# slave-board.net
KiCad netlist of a schematic drawn in EAGLE
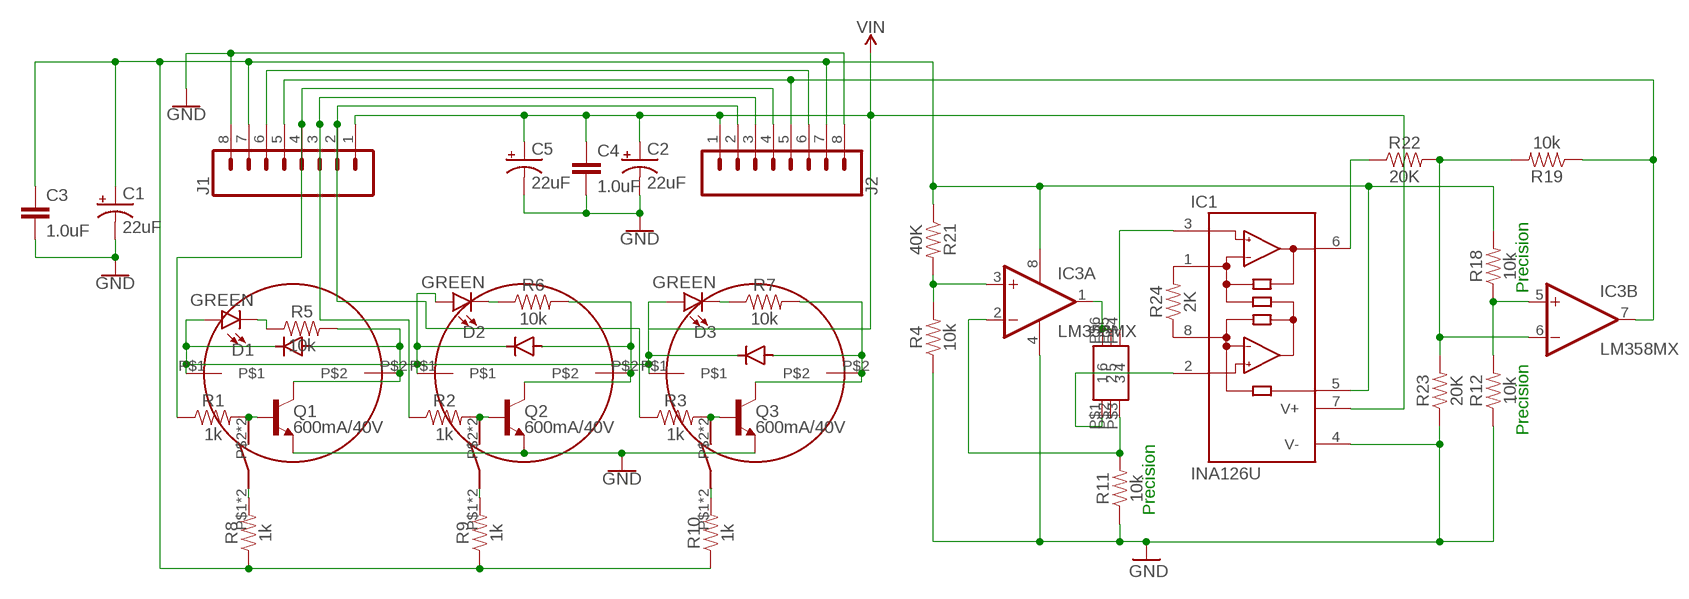
[diagram p0: schematic, sheet 1]

(export (version "E")
  (design (tool "Eeschema 10.0.6"))
  (components
    (comp (ref "C1")
      (value "22uF")
      (footprint "eagle-import:PANASONIC_C")
      (libsource (lib "eagle-import") (part "22UF-POLAR-PANASONIC_C-35V-20%"))
    )
    (comp (ref "C2")
      (value "22uF")
      (footprint "eagle-import:PANASONIC_C")
      (libsource (lib "eagle-import") (part "22UF-POLAR-PANASONIC_C-35V-20%"))
    )
    (comp (ref "C3")
      (value "1.0uF")
      (footprint "eagle-import:0603")
      (libsource (lib "eagle-import") (part "1.0UF-0603-16V-10%"))
    )
    (comp (ref "C4")
      (value "1.0uF")
      (footprint "eagle-import:0603")
      (libsource (lib "eagle-import") (part "1.0UF-0603-16V-10%"))
    )
    (comp (ref "C5")
      (value "22uF")
      (footprint "eagle-import:PANASONIC_C")
      (libsource (lib "eagle-import") (part "22UF-POLAR-PANASONIC_C-35V-20%"))
    )
    (comp (ref "D1")
      (value "GREEN")
      (footprint "eagle-import:LED-0603")
      (libsource (lib "eagle-import") (part "LED-GREEN0603"))
    )
    (comp (ref "D2")
      (value "GREEN")
      (footprint "eagle-import:LED-0603")
      (libsource (lib "eagle-import") (part "LED-GREEN0603"))
    )
    (comp (ref "D3")
      (value "GREEN")
      (footprint "eagle-import:LED-0603")
      (libsource (lib "eagle-import") (part "LED-GREEN0603"))
    )
    (comp (ref "IC1")
      (value "INA126U")
      (footprint "eagle-import:SO08")
      (fields (field (name "MF") "Texas Instruments") (field (name "MP") "INA126"))
      (libsource (lib "eagle-import") (part "INA126U"))
    )
    (comp (ref "IC3")
      (value "LM358MX")
      (footprint "eagle-import:SO08")
      (libsource (lib "eagle-import") (part "LM358MX"))
    )
    (comp (ref "J1")
      (value "CONN_08\"")
      (footprint "eagle-import:1X08")
      (libsource (lib "eagle-import") (part "CONN_08{dblquote}"))
    )
    (comp (ref "J2")
      (value "CONN_08\"")
      (footprint "eagle-import:1X08")
      (libsource (lib "eagle-import") (part "CONN_08{dblquote}"))
    )
    (comp (ref "Q1")
      (value "600mA/40V")
      (footprint "eagle-import:SOT23-3")
      (libsource (lib "eagle-import") (part "TRANS_NPN-MMBT2222AL"))
    )
    (comp (ref "Q2")
      (value "600mA/40V")
      (footprint "eagle-import:SOT23-3")
      (libsource (lib "eagle-import") (part "TRANS_NPN-MMBT2222AL"))
    )
    (comp (ref "Q3")
      (value "600mA/40V")
      (footprint "eagle-import:SOT23-3")
      (libsource (lib "eagle-import") (part "TRANS_NPN-MMBT2222AL"))
    )
    (comp (ref "R1")
      (value "1k")
      (footprint "eagle-import:0603")
      (libsource (lib "eagle-import") (part "1KOHM-0603-1/10W-1%"))
    )
    (comp (ref "R2")
      (value "1k")
      (footprint "eagle-import:0603")
      (libsource (lib "eagle-import") (part "1KOHM-0603-1/10W-1%"))
    )
    (comp (ref "R3")
      (value "1k")
      (footprint "eagle-import:0603")
      (libsource (lib "eagle-import") (part "1KOHM-0603-1/10W-1%"))
    )
    (comp (ref "R4")
      (value "10k")
      (footprint "eagle-import:0603")
      (libsource (lib "eagle-import") (part "10KOHM-0603-1/10W-1%"))
    )
    (comp (ref "R5")
      (value "10k")
      (footprint "eagle-import:0603")
      (libsource (lib "eagle-import") (part "10KOHM-0603-1/10W-1%"))
    )
    (comp (ref "R6")
      (value "10k")
      (footprint "eagle-import:0603")
      (libsource (lib "eagle-import") (part "10KOHM-0603-1/10W-1%"))
    )
    (comp (ref "R7")
      (value "10k")
      (footprint "eagle-import:0603")
      (libsource (lib "eagle-import") (part "10KOHM-0603-1/10W-1%"))
    )
    (comp (ref "R8")
      (value "1k")
      (footprint "eagle-import:0603")
      (libsource (lib "eagle-import") (part "1KOHM-0603-1/10W-1%"))
    )
    (comp (ref "R9")
      (value "1k")
      (footprint "eagle-import:0603")
      (libsource (lib "eagle-import") (part "1KOHM-0603-1/10W-1%"))
    )
    (comp (ref "R10")
      (value "1k")
      (footprint "eagle-import:0603")
      (libsource (lib "eagle-import") (part "1KOHM-0603-1/10W-1%"))
    )
    (comp (ref "R11")
      (value "10k")
      (footprint "eagle-import:0603")
      (libsource (lib "eagle-import") (part "10KOHM-0603-1/10W-1%"))
    )
    (comp (ref "R12")
      (value "10k")
      (footprint "eagle-import:0603")
      (libsource (lib "eagle-import") (part "10KOHM-0603-1/10W-1%"))
    )
    (comp (ref "R18")
      (value "10k")
      (footprint "eagle-import:0603")
      (libsource (lib "eagle-import") (part "10KOHM-0603-1/10W-1%"))
    )
    (comp (ref "R19")
      (value "10k")
      (footprint "eagle-import:0603")
      (libsource (lib "eagle-import") (part "10KOHM-0603-1/10W-1%"))
    )
    (comp (ref "R21")
      (value "40K")
      (footprint "eagle-import:0603")
      (libsource (lib "eagle-import") (part "10KOHM-0603-1/10W-1%"))
    )
    (comp (ref "R22")
      (value "20K")
      (footprint "eagle-import:0603")
      (libsource (lib "eagle-import") (part "10KOHM-0603-1/10W-1%"))
    )
    (comp (ref "R23")
      (value "20K")
      (footprint "eagle-import:0603")
      (libsource (lib "eagle-import") (part "10KOHM-0603-1/10W-1%"))
    )
    (comp (ref "R24")
      (value "2K")
      (footprint "eagle-import:0603")
      (libsource (lib "eagle-import") (part "10KOHM-0603-1/10W-1%"))
    )
    (comp (ref "U$1")
      (value "2SMPP-03")
      (footprint "eagle-import:2SMPP-03")
      (libsource (lib "eagle-import") (part "2SMPP-03"))
    )
    (comp (ref "U$2")
      (value "CJV23-SOLENOID-VALVE")
      (footprint "eagle-import:CJV23")
      (libsource (lib "eagle-import") (part "CJV23-SOLENOID-VALVE"))
    )
    (comp (ref "U$3")
      (value "CJV23-SOLENOID-VALVE")
      (footprint "eagle-import:CJV23")
      (libsource (lib "eagle-import") (part "CJV23-SOLENOID-VALVE"))
    )
    (comp (ref "U$4")
      (value "CJV23-SOLENOID-VALVE")
      (footprint "eagle-import:CJV23")
      (libsource (lib "eagle-import") (part "CJV23-SOLENOID-VALVE"))
    )
    (comp (ref "U$5")
      (value "IN4148")
      (footprint "eagle-import:IN4148")
      (libsource (lib "eagle-import") (part "IN4148"))
    )
    (comp (ref "U$6")
      (value "IN4148")
      (footprint "eagle-import:IN4148")
      (libsource (lib "eagle-import") (part "IN4148"))
    )
    (comp (ref "U$7")
      (value "IN4148")
      (footprint "eagle-import:IN4148")
      (libsource (lib "eagle-import") (part "IN4148"))
    )
    (comp (ref "U$8")
      (value "BUTTON")
      (footprint "eagle-import:BUTTON")
      (libsource (lib "eagle-import") (part "BUTTON"))
    )
    (comp (ref "U$9")
      (value "BUTTON")
      (footprint "eagle-import:BUTTON")
      (libsource (lib "eagle-import") (part "BUTTON"))
    )
    (comp (ref "U$10")
      (value "BUTTON")
      (footprint "eagle-import:BUTTON")
      (libsource (lib "eagle-import") (part "BUTTON"))
    )
  )
  (nets
    (net (code "1") (name "GND") (class "Default")
      (node (ref "C1") (pin "-") (pinfunction "-_-") (pintype "passive"))
      (node (ref "C2") (pin "-") (pinfunction "-_-") (pintype "passive"))
      (node (ref "C3") (pin "2") (pinfunction "2_2") (pintype "passive"))
      (node (ref "C4") (pin "2") (pinfunction "2_2") (pintype "passive"))
      (node (ref "C5") (pin "-") (pinfunction "-_-") (pintype "passive"))
      (node (ref "IC1") (pin "4") (pinfunction "V-_4") (pintype "power_in"))
      (node (ref "IC3") (pin "4") (pinfunction "V-_4") (pintype "power_in"))
      (node (ref "J1") (pin "8") (pinfunction "8_8") (pintype "passive"))
      (node (ref "J2") (pin "8") (pinfunction "8_8") (pintype "passive"))
      (node (ref "Q1") (pin "2") (pinfunction "E_2") (pintype "passive"))
      (node (ref "Q2") (pin "2") (pinfunction "E_2") (pintype "passive"))
      (node (ref "Q3") (pin "2") (pinfunction "E_2") (pintype "passive"))
      (node (ref "R11") (pin "1") (pinfunction "1_1") (pintype "passive"))
      (node (ref "R12") (pin "1") (pinfunction "1_1") (pintype "passive"))
      (node (ref "R23") (pin "1") (pinfunction "1_1") (pintype "passive"))
      (node (ref "R4") (pin "1") (pinfunction "1_1") (pintype "passive"))
    )
    (net (code "2") (name "Net-(D1-PadC)") (class "Default")
      (node (ref "D1") (pin "C") (pinfunction "C_C") (pintype "passive"))
      (node (ref "R5") (pin "1") (pinfunction "1_1") (pintype "passive"))
    )
    (net (code "3") (name "Net-(D2-PadC)") (class "Default")
      (node (ref "D2") (pin "C") (pinfunction "C_C") (pintype "passive"))
      (node (ref "R6") (pin "1") (pinfunction "1_1") (pintype "passive"))
    )
    (net (code "4") (name "Net-(D3-PadC)") (class "Default")
      (node (ref "D3") (pin "C") (pinfunction "C_C") (pintype "passive"))
      (node (ref "R7") (pin "1") (pinfunction "1_1") (pintype "passive"))
    )
    (net (code "5") (name "Net-(IC1-+IN)") (class "Default")
      (node (ref "IC1") (pin "3") (pinfunction "+IN_3") (pintype "input"))
      (node (ref "U$1") (pin "P$4") (pinfunction "4_P$4") (pintype "bidirectional"))
    )
    (net (code "6") (name "Net-(IC1--IN)") (class "Default")
      (node (ref "IC1") (pin "2") (pinfunction "-IN_2") (pintype "input"))
      (node (ref "U$1") (pin "P$1") (pinfunction "1_P$1") (pintype "bidirectional"))
    )
    (net (code "7") (name "Net-(IC1-OUT)") (class "Default")
      (node (ref "IC1") (pin "6") (pinfunction "OUT_6") (pintype "output"))
      (node (ref "R22") (pin "1") (pinfunction "1_1") (pintype "passive"))
    )
    (net (code "8") (name "Net-(IC1-REF)") (class "Default")
      (node (ref "C1") (pin "+") (pinfunction "+_+") (pintype "passive"))
      (node (ref "C3") (pin "1") (pinfunction "1_1") (pintype "passive"))
      (node (ref "IC1") (pin "5") (pinfunction "REF_5") (pintype "passive"))
      (node (ref "IC3") (pin "8") (pinfunction "V+_8") (pintype "power_in"))
      (node (ref "J1") (pin "7") (pinfunction "7_7") (pintype "passive"))
      (node (ref "J2") (pin "7") (pinfunction "7_7") (pintype "passive"))
      (node (ref "R10") (pin "1") (pinfunction "1_1") (pintype "passive"))
      (node (ref "R18") (pin "2") (pinfunction "2_2") (pintype "passive"))
      (node (ref "R21") (pin "1") (pinfunction "1_1") (pintype "passive"))
      (node (ref "R8") (pin "1") (pinfunction "1_1") (pintype "passive"))
      (node (ref "R9") (pin "1") (pinfunction "1_1") (pintype "passive"))
    )
    (net (code "9") (name "Net-(IC1-RG-Pad1)") (class "Default")
      (node (ref "IC1") (pin "1") (pinfunction "RG_1") (pintype "passive"))
      (node (ref "R24") (pin "2") (pinfunction "2_2") (pintype "passive"))
    )
    (net (code "10") (name "Net-(IC1-RG-Pad8)") (class "Default")
      (node (ref "IC1") (pin "8") (pinfunction "RG_8") (pintype "passive"))
      (node (ref "R24") (pin "1") (pinfunction "1_1") (pintype "passive"))
    )
    (net (code "11") (name "Net-(IC3A-+IN)") (class "Default")
      (node (ref "IC3") (pin "3") (pinfunction "+IN_3") (pintype "input"))
      (node (ref "R21") (pin "2") (pinfunction "2_2") (pintype "passive"))
      (node (ref "R4") (pin "2") (pinfunction "2_2") (pintype "passive"))
    )
    (net (code "12") (name "Net-(IC3A--IN)") (class "Default")
      (node (ref "IC3") (pin "2") (pinfunction "-IN_2") (pintype "input"))
      (node (ref "R11") (pin "2") (pinfunction "2_2") (pintype "passive"))
      (node (ref "U$1") (pin "P$3") (pinfunction "3_P$3") (pintype "bidirectional"))
    )
    (net (code "13") (name "Net-(IC3A-OUT)") (class "Default")
      (node (ref "IC3") (pin "1") (pinfunction "OUT_1") (pintype "output"))
      (node (ref "U$1") (pin "P$5") (pinfunction "5_P$5") (pintype "bidirectional"))
      (node (ref "U$1") (pin "P$6") (pinfunction "6_P$6") (pintype "bidirectional"))
    )
    (net (code "14") (name "Net-(IC3B-+IN)") (class "Default")
      (node (ref "IC3") (pin "5") (pinfunction "+IN_5") (pintype "input"))
      (node (ref "R12") (pin "2") (pinfunction "2_2") (pintype "passive"))
      (node (ref "R18") (pin "1") (pinfunction "1_1") (pintype "passive"))
    )
    (net (code "15") (name "Net-(IC3B--IN)") (class "Default")
      (node (ref "IC3") (pin "6") (pinfunction "-IN_6") (pintype "input"))
      (node (ref "R19") (pin "2") (pinfunction "2_2") (pintype "passive"))
      (node (ref "R22") (pin "2") (pinfunction "2_2") (pintype "passive"))
      (node (ref "R23") (pin "2") (pinfunction "2_2") (pintype "passive"))
    )
    (net (code "16") (name "Net-(IC3B-OUT)") (class "Default")
      (node (ref "IC3") (pin "7") (pinfunction "OUT_7") (pintype "output"))
      (node (ref "J1") (pin "5") (pinfunction "5_5") (pintype "passive"))
      (node (ref "J2") (pin "5") (pinfunction "5_5") (pintype "passive"))
      (node (ref "R19") (pin "1") (pinfunction "1_1") (pintype "passive"))
    )
    (net (code "17") (name "Net-(J1-Pad2)") (class "Default")
      (node (ref "J1") (pin "2") (pinfunction "2_2") (pintype "passive"))
      (node (ref "J2") (pin "2") (pinfunction "2_2") (pintype "passive"))
      (node (ref "R3") (pin "1") (pinfunction "1_1") (pintype "passive"))
    )
    (net (code "18") (name "Net-(J1-Pad3)") (class "Default")
      (node (ref "J1") (pin "3") (pinfunction "3_3") (pintype "passive"))
      (node (ref "J2") (pin "3") (pinfunction "3_3") (pintype "passive"))
      (node (ref "R2") (pin "1") (pinfunction "1_1") (pintype "passive"))
    )
    (net (code "19") (name "Net-(J1-Pad4)") (class "Default")
      (node (ref "J1") (pin "4") (pinfunction "4_4") (pintype "passive"))
      (node (ref "J2") (pin "4") (pinfunction "4_4") (pintype "passive"))
      (node (ref "R1") (pin "1") (pinfunction "1_1") (pintype "passive"))
    )
    (net (code "20") (name "Net-(J1-Pad6)") (class "Default")
      (node (ref "J1") (pin "6") (pinfunction "6_6") (pintype "passive"))
      (node (ref "J2") (pin "6") (pinfunction "6_6") (pintype "passive"))
    )
    (net (code "21") (name "Net-(Q1-B)") (class "Default")
      (node (ref "Q1") (pin "1") (pinfunction "B_1") (pintype "passive"))
      (node (ref "R1") (pin "2") (pinfunction "2_2") (pintype "passive"))
      (node (ref "U$8") (pin "P$2") (pinfunction "P$2_P$2") (pintype "bidirectional"))
      (node (ref "U$8") (pin "P$4") (pinfunction "P$2_P$4") (pintype "bidirectional"))
    )
    (net (code "22") (name "Net-(Q1-C)") (class "Default")
      (node (ref "Q1") (pin "3") (pinfunction "C_3") (pintype "passive"))
      (node (ref "R5") (pin "2") (pinfunction "2_2") (pintype "passive"))
      (node (ref "U$2") (pin "P$2") (pinfunction "P$2_P$2") (pintype "bidirectional"))
      (node (ref "U$5") (pin "P$2") (pinfunction "P$2_P$2") (pintype "bidirectional"))
    )
    (net (code "23") (name "Net-(Q2-B)") (class "Default")
      (node (ref "Q2") (pin "1") (pinfunction "B_1") (pintype "passive"))
      (node (ref "R2") (pin "2") (pinfunction "2_2") (pintype "passive"))
      (node (ref "U$9") (pin "P$2") (pinfunction "P$2_P$2") (pintype "bidirectional"))
      (node (ref "U$9") (pin "P$4") (pinfunction "P$2_P$4") (pintype "bidirectional"))
    )
    (net (code "24") (name "Net-(Q2-C)") (class "Default")
      (node (ref "Q2") (pin "3") (pinfunction "C_3") (pintype "passive"))
      (node (ref "R6") (pin "2") (pinfunction "2_2") (pintype "passive"))
      (node (ref "U$3") (pin "P$2") (pinfunction "P$2_P$2") (pintype "bidirectional"))
      (node (ref "U$6") (pin "P$2") (pinfunction "P$2_P$2") (pintype "bidirectional"))
    )
    (net (code "25") (name "Net-(Q3-B)") (class "Default")
      (node (ref "Q3") (pin "1") (pinfunction "B_1") (pintype "passive"))
      (node (ref "R3") (pin "2") (pinfunction "2_2") (pintype "passive"))
      (node (ref "U$10") (pin "P$2") (pinfunction "P$2_P$2") (pintype "bidirectional"))
      (node (ref "U$10") (pin "P$4") (pinfunction "P$2_P$4") (pintype "bidirectional"))
    )
    (net (code "26") (name "Net-(Q3-C)") (class "Default")
      (node (ref "Q3") (pin "3") (pinfunction "C_3") (pintype "passive"))
      (node (ref "R7") (pin "2") (pinfunction "2_2") (pintype "passive"))
      (node (ref "U$4") (pin "P$2") (pinfunction "P$2_P$2") (pintype "bidirectional"))
      (node (ref "U$7") (pin "P$2") (pinfunction "P$2_P$2") (pintype "bidirectional"))
    )
    (net (code "27") (name "Net-(R8-Pad2)") (class "Default")
      (node (ref "R8") (pin "2") (pinfunction "2_2") (pintype "passive"))
      (node (ref "U$8") (pin "P$1") (pinfunction "P$1_P$1") (pintype "bidirectional"))
      (node (ref "U$8") (pin "P$3") (pinfunction "P$1_P$3") (pintype "bidirectional"))
    )
    (net (code "28") (name "Net-(R9-Pad2)") (class "Default")
      (node (ref "R9") (pin "2") (pinfunction "2_2") (pintype "passive"))
      (node (ref "U$9") (pin "P$1") (pinfunction "P$1_P$1") (pintype "bidirectional"))
      (node (ref "U$9") (pin "P$3") (pinfunction "P$1_P$3") (pintype "bidirectional"))
    )
    (net (code "29") (name "Net-(R10-Pad2)") (class "Default")
      (node (ref "R10") (pin "2") (pinfunction "2_2") (pintype "passive"))
      (node (ref "U$10") (pin "P$1") (pinfunction "P$1_P$1") (pintype "bidirectional"))
      (node (ref "U$10") (pin "P$3") (pinfunction "P$1_P$3") (pintype "bidirectional"))
    )
    (net (code "30") (name "VIN") (class "Default")
      (node (ref "C2") (pin "+") (pinfunction "+_+") (pintype "passive"))
      (node (ref "C4") (pin "1") (pinfunction "1_1") (pintype "passive"))
      (node (ref "C5") (pin "+") (pinfunction "+_+") (pintype "passive"))
      (node (ref "D1") (pin "A") (pinfunction "A_A") (pintype "passive"))
      (node (ref "D2") (pin "A") (pinfunction "A_A") (pintype "passive"))
      (node (ref "D3") (pin "A") (pinfunction "A_A") (pintype "passive"))
      (node (ref "IC1") (pin "7") (pinfunction "V+_7") (pintype "power_in"))
      (node (ref "J1") (pin "1") (pinfunction "1_1") (pintype "passive"))
      (node (ref "J2") (pin "1") (pinfunction "1_1") (pintype "passive"))
      (node (ref "U$2") (pin "P$1") (pinfunction "P$1_P$1") (pintype "bidirectional"))
      (node (ref "U$3") (pin "P$1") (pinfunction "P$1_P$1") (pintype "bidirectional"))
      (node (ref "U$4") (pin "P$1") (pinfunction "P$1_P$1") (pintype "bidirectional"))
      (node (ref "U$5") (pin "P$1") (pinfunction "P$1_P$1") (pintype "bidirectional"))
      (node (ref "U$6") (pin "P$1") (pinfunction "P$1_P$1") (pintype "bidirectional"))
      (node (ref "U$7") (pin "P$1") (pinfunction "P$1_P$1") (pintype "bidirectional"))
    )
    (net (code "31") (name "unconnected-(U$1-2-PadP$2)") (class "Default")
      (node (ref "U$1") (pin "P$2") (pinfunction "2_P$2") (pintype "bidirectional"))
    )
  )
)
